# RS485.net
KiCad netlist of a schematic drawn in Altium Designer
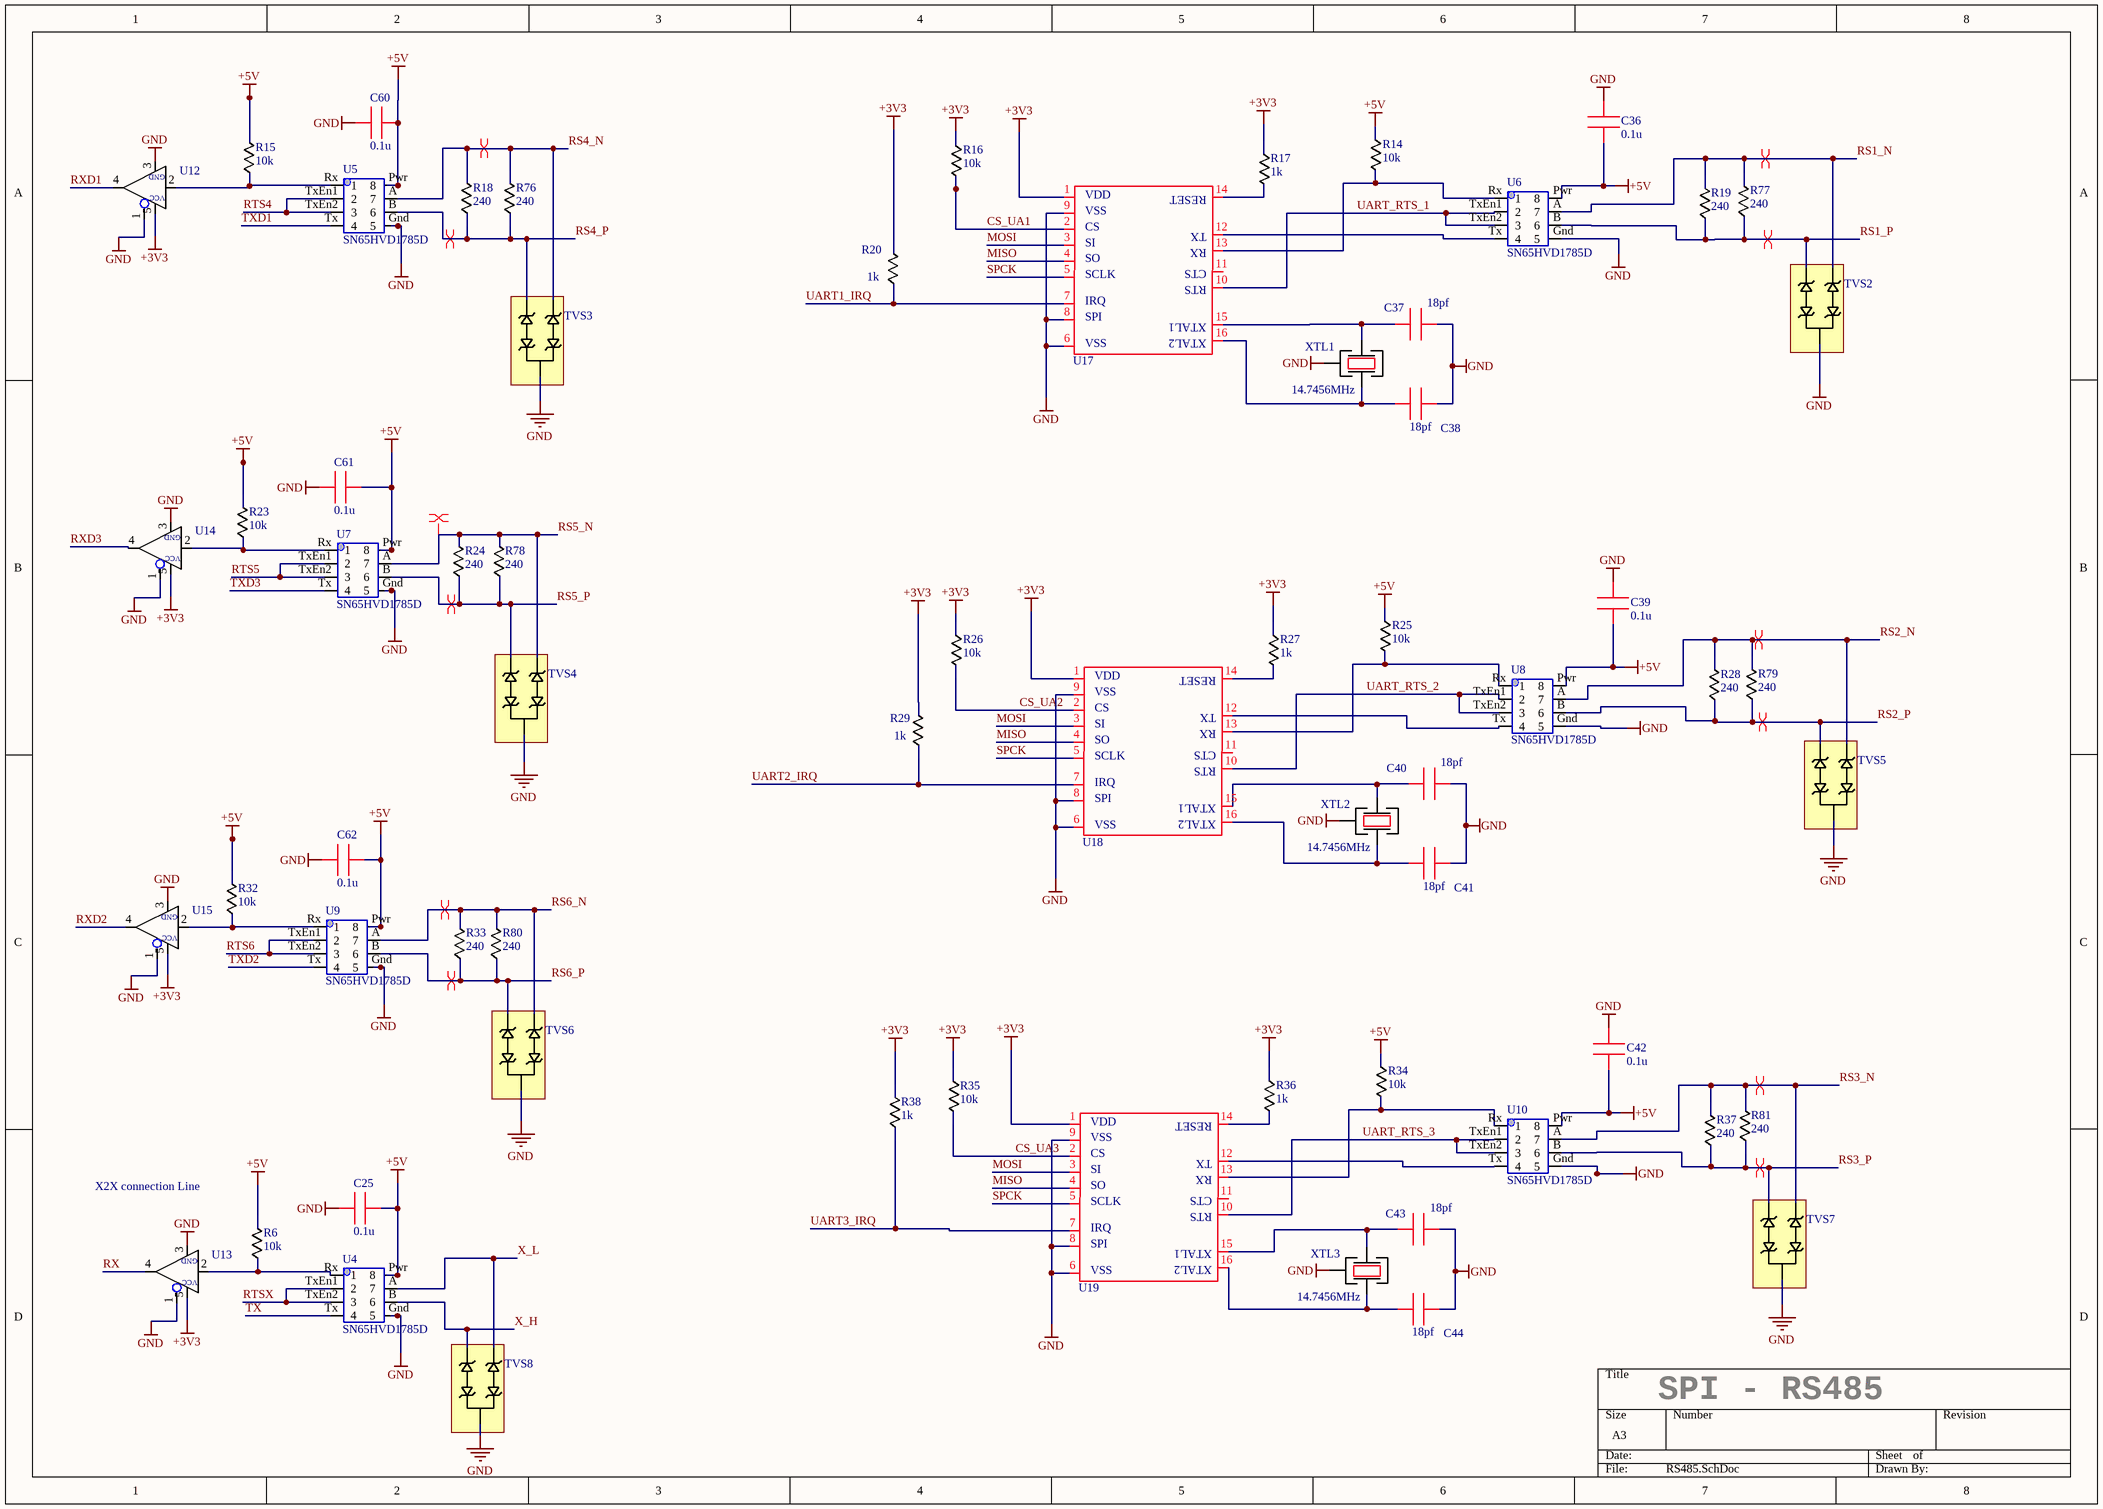
[diagram p0: RS485.SchDoc]

(export (version "E")
  (design (tool "Eeschema 10.0.6"))
  (components
    (comp (ref "C25") (value "0.1u") (footprint "0603 CAP") (libsource (lib "kontr") (part "Capasitor 0805")))
    (comp (ref "C36") (value "0.1u") (footprint "0603 CAP") (libsource (lib "kontr") (part "Capasitor 0805")))
    (comp (ref "C37")
      (value "18pf")
      (footprint "0603 CAP")
      (description "GRM1885C1H180JA01D")
      (libsource (lib "kontr") (part "Capasitor 0805"))
    )
    (comp (ref "C38")
      (value "18pf")
      (footprint "0603 CAP")
      (description "GRM1885C1H180JA01D")
      (libsource (lib "kontr") (part "Capasitor 0805"))
    )
    (comp (ref "C39") (value "0.1u") (footprint "0603 CAP") (libsource (lib "kontr") (part "Capasitor 0805")))
    (comp (ref "C40")
      (value "18pf")
      (footprint "0603 CAP")
      (description "GRM1885C1H180JA01D")
      (libsource (lib "kontr") (part "Capasitor 0805"))
    )
    (comp (ref "C41")
      (value "18pf")
      (footprint "0603 CAP")
      (description "GRM1885C1H180JA01D")
      (libsource (lib "kontr") (part "Capasitor 0805"))
    )
    (comp (ref "C42") (value "0.1u") (footprint "0603 CAP") (libsource (lib "kontr") (part "Capasitor 0805")))
    (comp (ref "C43")
      (value "18pf")
      (footprint "0603 CAP")
      (description "GRM1885C1H180JA01D")
      (libsource (lib "kontr") (part "Capasitor 0805"))
    )
    (comp (ref "C44")
      (value "18pf")
      (footprint "0603 CAP")
      (description "GRM1885C1H180JA01D")
      (libsource (lib "kontr") (part "Capasitor 0805"))
    )
    (comp (ref "C60") (value "0.1u") (footprint "0603 CAP") (libsource (lib "kontr") (part "Capasitor 0805")))
    (comp (ref "C61") (value "0.1u") (footprint "0603 CAP") (libsource (lib "kontr") (part "Capasitor 0805")))
    (comp (ref "C62") (value "0.1u") (footprint "0603 CAP") (libsource (lib "kontr") (part "Capasitor 0805")))
    (comp (ref "R6")
      (value "10k")
      (footprint "0603 - RES")
      (description "RC0603FR-078K2")
      (libsource (lib "kontr") (part "Resistor 0805"))
    )
    (comp (ref "R14")
      (value "10k")
      (footprint "0603 - RES")
      (description "RC0603FR-078K2")
      (libsource (lib "kontr") (part "Resistor 0805"))
    )
    (comp (ref "R15")
      (value "10k")
      (footprint "0603 - RES")
      (description "RC0603FR-078K2")
      (libsource (lib "kontr") (part "Resistor 0805"))
    )
    (comp (ref "R16")
      (value "10k")
      (footprint "0603 - RES")
      (description "RC0603JR-0710K")
      (libsource (lib "kontr") (part "Resistor 0805"))
    )
    (comp (ref "R17")
      (value "1k")
      (footprint "0603 - RES")
      (description "RC0603JR-0710K")
      (libsource (lib "kontr") (part "Resistor 0805"))
    )
    (comp (ref "R18")
      (value "240")
      (footprint "0603 - RES")
      (description "RC0603JR-07120R")
      (libsource (lib "kontr") (part "Resistor 0805"))
    )
    (comp (ref "R19")
      (value "240")
      (footprint "0603 - RES")
      (description "RC0603JR-07120R")
      (libsource (lib "kontr") (part "Resistor 0805"))
    )
    (comp (ref "R20")
      (value "1k")
      (footprint "0603 - RES")
      (description "RC0603JR-0710K")
      (libsource (lib "kontr") (part "Resistor 0805"))
    )
    (comp (ref "R23")
      (value "10k")
      (footprint "0603 - RES")
      (description "RC0603FR-078K2")
      (libsource (lib "kontr") (part "Resistor 0805"))
    )
    (comp (ref "R24")
      (value "240")
      (footprint "0603 - RES")
      (description "RC0603JR-07120R")
      (libsource (lib "kontr") (part "Resistor 0805"))
    )
    (comp (ref "R25")
      (value "10k")
      (footprint "0603 - RES")
      (description "RC0603FR-078K2")
      (libsource (lib "kontr") (part "Resistor 0805"))
    )
    (comp (ref "R26")
      (value "10k")
      (footprint "0603 - RES")
      (description "RC0603JR-0710K")
      (libsource (lib "kontr") (part "Resistor 0805"))
    )
    (comp (ref "R27")
      (value "1k")
      (footprint "0603 - RES")
      (description "RC0603JR-0710K")
      (libsource (lib "kontr") (part "Resistor 0805"))
    )
    (comp (ref "R28")
      (value "240")
      (footprint "0603 - RES")
      (description "RC0603JR-07120R")
      (libsource (lib "kontr") (part "Resistor 0805"))
    )
    (comp (ref "R29")
      (value "1k")
      (footprint "0603 - RES")
      (description "RC0603JR-0710K")
      (libsource (lib "kontr") (part "Resistor 0805"))
    )
    (comp (ref "R32")
      (value "10k")
      (footprint "0603 - RES")
      (description "RC0603FR-078K2")
      (libsource (lib "kontr") (part "Resistor 0805"))
    )
    (comp (ref "R33")
      (value "240")
      (footprint "0603 - RES")
      (description "RC0603JR-07120R")
      (libsource (lib "kontr") (part "Resistor 0805"))
    )
    (comp (ref "R34")
      (value "10k")
      (footprint "0603 - RES")
      (description "RC0603FR-078K2")
      (libsource (lib "kontr") (part "Resistor 0805"))
    )
    (comp (ref "R35")
      (value "10k")
      (footprint "0603 - RES")
      (description "RC0603JR-0710K")
      (libsource (lib "kontr") (part "Resistor 0805"))
    )
    (comp (ref "R36")
      (value "1k")
      (footprint "0603 - RES")
      (description "RC0603JR-0710K")
      (libsource (lib "kontr") (part "Resistor 0805"))
    )
    (comp (ref "R37")
      (value "240")
      (footprint "0603 - RES")
      (description "RC0603JR-07120R")
      (libsource (lib "kontr") (part "Resistor 0805"))
    )
    (comp (ref "R38")
      (value "1k")
      (footprint "0603 - RES")
      (description "RC0603JR-0710K")
      (libsource (lib "kontr") (part "Resistor 0805"))
    )
    (comp (ref "R76")
      (value "240")
      (footprint "0603 - RES")
      (description "RC0603JR-07120R")
      (libsource (lib "kontr") (part "Resistor 0805"))
    )
    (comp (ref "R77")
      (value "240")
      (footprint "0603 - RES")
      (description "RC0603JR-07120R")
      (libsource (lib "kontr") (part "Resistor 0805"))
    )
    (comp (ref "R78")
      (value "240")
      (footprint "0603 - RES")
      (description "RC0603JR-07120R")
      (libsource (lib "kontr") (part "Resistor 0805"))
    )
    (comp (ref "R79")
      (value "240")
      (footprint "0603 - RES")
      (description "RC0603JR-07120R")
      (libsource (lib "kontr") (part "Resistor 0805"))
    )
    (comp (ref "R80")
      (value "240")
      (footprint "0603 - RES")
      (description "RC0603JR-07120R")
      (libsource (lib "kontr") (part "Resistor 0805"))
    )
    (comp (ref "R81")
      (value "240")
      (footprint "0603 - RES")
      (description "RC0603JR-07120R")
      (libsource (lib "kontr") (part "Resistor 0805"))
    )
    (comp (ref "TVS2")
      (value "CDSOT23-SM712")
      (footprint "Sot23-3")
      (libsource (lib "kontr") (part "CDSOT23-SM712"))
    )
    (comp (ref "TVS3")
      (value "CDSOT23-SM712")
      (footprint "Sot23-3")
      (libsource (lib "kontr") (part "CDSOT23-SM712"))
    )
    (comp (ref "TVS4")
      (value "CDSOT23-SM712")
      (footprint "Sot23-3")
      (libsource (lib "kontr") (part "CDSOT23-SM712"))
    )
    (comp (ref "TVS5")
      (value "CDSOT23-SM712")
      (footprint "Sot23-3")
      (libsource (lib "kontr") (part "CDSOT23-SM712"))
    )
    (comp (ref "TVS6")
      (value "CDSOT23-SM712")
      (footprint "Sot23-3")
      (libsource (lib "kontr") (part "CDSOT23-SM712"))
    )
    (comp (ref "TVS7")
      (value "CDSOT23-SM712")
      (footprint "Sot23-3")
      (libsource (lib "kontr") (part "CDSOT23-SM712"))
    )
    (comp (ref "TVS8")
      (value "CDSOT23-SM712")
      (footprint "Sot23-3")
      (libsource (lib "kontr") (part "CDSOT23-SM712"))
    )
    (comp (ref "U4")
      (value "SN65HVD1785D")
      (footprint "MAX485 - duplicate")
      (libsource (lib "Schlib1") (part "MAX485"))
    )
    (comp (ref "U5")
      (value "SN65HVD1785D")
      (footprint "MAX485 - duplicate")
      (libsource (lib "Schlib1") (part "MAX485"))
    )
    (comp (ref "U6")
      (value "SN65HVD1785D")
      (footprint "MAX485 - duplicate")
      (libsource (lib "Schlib1") (part "MAX485"))
    )
    (comp (ref "U7")
      (value "SN65HVD1785D")
      (footprint "MAX485 - duplicate")
      (libsource (lib "Schlib1") (part "MAX485"))
    )
    (comp (ref "U8")
      (value "SN65HVD1785D")
      (footprint "MAX485 - duplicate")
      (libsource (lib "Schlib1") (part "MAX485"))
    )
    (comp (ref "U9")
      (value "SN65HVD1785D")
      (footprint "MAX485 - duplicate")
      (libsource (lib "Schlib1") (part "MAX485"))
    )
    (comp (ref "U10")
      (value "SN65HVD1785D")
      (footprint "MAX485 - duplicate")
      (libsource (lib "Schlib1") (part "MAX485"))
    )
    (comp (ref "U12")
      (value "74LVC1G125DCK")
      (footprint "74LVC1G125DCK")
      (libsource (lib "kontr") (part "74LVC1G125DCK"))
    )
    (comp (ref "U13")
      (value "74LVC1G125DCK")
      (footprint "74LVC1G125DCK")
      (libsource (lib "kontr") (part "74LVC1G125DCK"))
    )
    (comp (ref "U14")
      (value "74LVC1G125DCK")
      (footprint "74LVC1G125DCK")
      (libsource (lib "kontr") (part "74LVC1G125DCK"))
    )
    (comp (ref "U15")
      (value "74LVC1G125DCK")
      (footprint "74LVC1G125DCK")
      (libsource (lib "kontr") (part "74LVC1G125DCK"))
    )
    (comp (ref "U17")
      (value "SC16IS740")
      (footprint "SC16IS740")
      (libsource (lib "kontr") (part "SC16IS740"))
    )
    (comp (ref "U18")
      (value "SC16IS740")
      (footprint "SC16IS740")
      (libsource (lib "kontr") (part "SC16IS740"))
    )
    (comp (ref "U19")
      (value "SC16IS740")
      (footprint "SC16IS740")
      (libsource (lib "kontr") (part "SC16IS740"))
    )
    (comp (ref "XTL1")
      (value "14.7456MHz")
      (footprint "XTAL KX-7T")
      (description "Geyer KX-7 14.7456MHz")
      (libsource (lib "") (part "KX-7_1"))
    )
    (comp (ref "XTL2")
      (value "14.7456MHz")
      (footprint "XTAL KX-7T")
      (description "Geyer KX-7 14.7456MHz")
      (libsource (lib "PLC M3") (part "KX-7"))
    )
    (comp (ref "XTL3")
      (value "14.7456MHz")
      (footprint "XTAL KX-7T")
      (description "Geyer KX-7 14.7456MHz")
      (libsource (lib "") (part "KX-7_1"))
    )
  )
  (nets
    (net (code "1") (name "+3V3") (class "Default")
      (node (ref "R16") (pin "1") (pintype "passive"))
      (node (ref "R17") (pin "1") (pintype "passive"))
      (node (ref "R20") (pin "2") (pintype "passive"))
      (node (ref "R26") (pin "1") (pintype "passive"))
      (node (ref "R27") (pin "1") (pintype "passive"))
      (node (ref "R29") (pin "2") (pintype "passive"))
      (node (ref "R35") (pin "1") (pintype "passive"))
      (node (ref "R36") (pin "1") (pintype "passive"))
      (node (ref "R38") (pin "2") (pintype "passive"))
      (node (ref "U12") (pin "5") (pinfunction "7_5") (pintype "passive"))
      (node (ref "U13") (pin "5") (pinfunction "7_5") (pintype "passive"))
      (node (ref "U14") (pin "5") (pinfunction "7_5") (pintype "passive"))
      (node (ref "U15") (pin "5") (pinfunction "7_5") (pintype "passive"))
      (node (ref "U17") (pin "1") (pinfunction "4_1") (pintype "passive"))
      (node (ref "U18") (pin "1") (pinfunction "4_1") (pintype "passive"))
      (node (ref "U19") (pin "1") (pinfunction "4_1") (pintype "passive"))
    )
    (net (code "2") (name "+5V") (class "Default")
      (node (ref "C25") (pin "2") (pinfunction "2_2") (pintype "passive"))
      (node (ref "C36") (pin "2") (pinfunction "2_2") (pintype "passive"))
      (node (ref "C39") (pin "2") (pinfunction "2_2") (pintype "passive"))
      (node (ref "C42") (pin "2") (pinfunction "2_2") (pintype "passive"))
      (node (ref "C60") (pin "2") (pinfunction "2_2") (pintype "passive"))
      (node (ref "C61") (pin "2") (pinfunction "2_2") (pintype "passive"))
      (node (ref "C62") (pin "2") (pinfunction "2_2") (pintype "passive"))
      (node (ref "R14") (pin "1") (pintype "passive"))
      (node (ref "R15") (pin "2") (pintype "passive"))
      (node (ref "R23") (pin "2") (pintype "passive"))
      (node (ref "R25") (pin "1") (pintype "passive"))
      (node (ref "R32") (pin "2") (pintype "passive"))
      (node (ref "R34") (pin "1") (pintype "passive"))
      (node (ref "R6") (pin "2") (pintype "passive"))
      (node (ref "U10") (pin "Pwr") (pinfunction "8_Pwr") (pintype "passive"))
      (node (ref "U4") (pin "Pwr") (pinfunction "8_Pwr") (pintype "passive"))
      (node (ref "U5") (pin "Pwr") (pinfunction "8_Pwr") (pintype "passive"))
      (node (ref "U6") (pin "Pwr") (pinfunction "8_Pwr") (pintype "passive"))
      (node (ref "U7") (pin "Pwr") (pinfunction "8_Pwr") (pintype "passive"))
      (node (ref "U8") (pin "Pwr") (pinfunction "8_Pwr") (pintype "passive"))
      (node (ref "U9") (pin "Pwr") (pinfunction "8_Pwr") (pintype "passive"))
    )
    (net (code "3") (name "/CS_UA1") (class "Default")
      (node (ref "R16") (pin "2") (pintype "passive"))
      (node (ref "U17") (pin "2") (pinfunction "8_2") (pintype "passive"))
    )
    (net (code "4") (name "/CS_UA2") (class "Default")
      (node (ref "R26") (pin "2") (pintype "passive"))
      (node (ref "U18") (pin "2") (pinfunction "8_2") (pintype "passive"))
    )
    (net (code "5") (name "/CS_UA3") (class "Default")
      (node (ref "R35") (pin "2") (pintype "passive"))
      (node (ref "U19") (pin "2") (pinfunction "8_2") (pintype "passive"))
    )
    (net (code "6") (name "/MISO") (class "Default")
      (node (ref "U17") (pin "4") (pinfunction "8_4") (pintype "passive"))
      (node (ref "U18") (pin "4") (pinfunction "8_4") (pintype "passive"))
      (node (ref "U19") (pin "4") (pinfunction "8_4") (pintype "passive"))
    )
    (net (code "7") (name "/MOSI") (class "Default")
      (node (ref "U17") (pin "3") (pinfunction "8_3") (pintype "passive"))
      (node (ref "U18") (pin "3") (pinfunction "8_3") (pintype "passive"))
      (node (ref "U19") (pin "3") (pinfunction "8_3") (pintype "passive"))
    )
    (net (code "8") (name "/RS1_N") (class "Default")
      (node (ref "R19") (pin "2") (pintype "passive"))
      (node (ref "R77") (pin "2") (pintype "passive"))
      (node (ref "TVS2") (pin "1") (pinfunction "1_1") (pintype "passive"))
      (node (ref "U6") (pin "A") (pinfunction "7_A") (pintype "passive"))
    )
    (net (code "9") (name "/RS1_P") (class "Default")
      (node (ref "R19") (pin "1") (pintype "passive"))
      (node (ref "R77") (pin "1") (pintype "passive"))
      (node (ref "TVS2") (pin "2") (pinfunction "2_2") (pintype "passive"))
      (node (ref "U6") (pin "B") (pinfunction "6_B") (pintype "passive"))
    )
    (net (code "10") (name "/RS2_N") (class "Default")
      (node (ref "R28") (pin "2") (pintype "passive"))
      (node (ref "R79") (pin "2") (pintype "passive"))
      (node (ref "TVS5") (pin "1") (pinfunction "1_1") (pintype "passive"))
      (node (ref "U8") (pin "A") (pinfunction "7_A") (pintype "passive"))
    )
    (net (code "11") (name "/RS2_P") (class "Default")
      (node (ref "R28") (pin "1") (pintype "passive"))
      (node (ref "R79") (pin "1") (pintype "passive"))
      (node (ref "TVS5") (pin "2") (pinfunction "2_2") (pintype "passive"))
      (node (ref "U8") (pin "B") (pinfunction "6_B") (pintype "passive"))
    )
    (net (code "12") (name "/RS3_N") (class "Default")
      (node (ref "R37") (pin "2") (pintype "passive"))
      (node (ref "R81") (pin "2") (pintype "passive"))
      (node (ref "TVS7") (pin "1") (pinfunction "1_1") (pintype "passive"))
      (node (ref "U10") (pin "A") (pinfunction "7_A") (pintype "passive"))
    )
    (net (code "13") (name "/RS3_P") (class "Default")
      (node (ref "R37") (pin "1") (pintype "passive"))
      (node (ref "R81") (pin "1") (pintype "passive"))
      (node (ref "TVS7") (pin "2") (pinfunction "2_2") (pintype "passive"))
      (node (ref "U10") (pin "B") (pinfunction "6_B") (pintype "passive"))
    )
    (net (code "14") (name "/RS4_N") (class "Default")
      (node (ref "R18") (pin "2") (pintype "passive"))
      (node (ref "R76") (pin "2") (pintype "passive"))
      (node (ref "TVS3") (pin "1") (pinfunction "1_1") (pintype "passive"))
      (node (ref "U5") (pin "A") (pinfunction "7_A") (pintype "passive"))
    )
    (net (code "15") (name "/RS4_P") (class "Default")
      (node (ref "R18") (pin "1") (pintype "passive"))
      (node (ref "R76") (pin "1") (pintype "passive"))
      (node (ref "TVS3") (pin "2") (pinfunction "2_2") (pintype "passive"))
      (node (ref "U5") (pin "B") (pinfunction "6_B") (pintype "passive"))
    )
    (net (code "16") (name "/RS5_N") (class "Default")
      (node (ref "R24") (pin "2") (pintype "passive"))
      (node (ref "R78") (pin "2") (pintype "passive"))
      (node (ref "TVS4") (pin "1") (pinfunction "1_1") (pintype "passive"))
      (node (ref "U7") (pin "A") (pinfunction "7_A") (pintype "passive"))
    )
    (net (code "17") (name "/RS5_P") (class "Default")
      (node (ref "R24") (pin "1") (pintype "passive"))
      (node (ref "R78") (pin "1") (pintype "passive"))
      (node (ref "TVS4") (pin "2") (pinfunction "2_2") (pintype "passive"))
      (node (ref "U7") (pin "B") (pinfunction "6_B") (pintype "passive"))
    )
    (net (code "18") (name "/RS6_N") (class "Default")
      (node (ref "R33") (pin "2") (pintype "passive"))
      (node (ref "R80") (pin "2") (pintype "passive"))
      (node (ref "TVS6") (pin "1") (pinfunction "1_1") (pintype "passive"))
      (node (ref "U9") (pin "A") (pinfunction "7_A") (pintype "passive"))
    )
    (net (code "19") (name "/RS6_P") (class "Default")
      (node (ref "R33") (pin "1") (pintype "passive"))
      (node (ref "R80") (pin "1") (pintype "passive"))
      (node (ref "TVS6") (pin "2") (pinfunction "2_2") (pintype "passive"))
      (node (ref "U9") (pin "B") (pinfunction "6_B") (pintype "passive"))
    )
    (net (code "20") (name "/RTS4") (class "Default")
      (node (ref "U5") (pin "TxEn1") (pinfunction "2_TxEn1") (pintype "passive"))
      (node (ref "U5") (pin "TxEn2") (pinfunction "3_TxEn2") (pintype "passive"))
    )
    (net (code "21") (name "/RTS5") (class "Default")
      (node (ref "U7") (pin "TxEn1") (pinfunction "2_TxEn1") (pintype "passive"))
      (node (ref "U7") (pin "TxEn2") (pinfunction "3_TxEn2") (pintype "passive"))
    )
    (net (code "22") (name "/RTS6") (class "Default")
      (node (ref "U9") (pin "TxEn1") (pinfunction "2_TxEn1") (pintype "passive"))
      (node (ref "U9") (pin "TxEn2") (pinfunction "3_TxEn2") (pintype "passive"))
    )
    (net (code "23") (name "/RTSX") (class "Default")
      (node (ref "U4") (pin "TxEn1") (pinfunction "2_TxEn1") (pintype "passive"))
      (node (ref "U4") (pin "TxEn2") (pinfunction "3_TxEn2") (pintype "passive"))
    )
    (net (code "24") (name "/RX") (class "Default")
      (node (ref "U13") (pin "4") (pinfunction "7_4") (pintype "passive"))
    )
    (net (code "25") (name "/RXD1") (class "Default")
      (node (ref "U12") (pin "4") (pinfunction "7_4") (pintype "passive"))
    )
    (net (code "26") (name "/RXD2") (class "Default")
      (node (ref "U15") (pin "4") (pinfunction "7_4") (pintype "passive"))
    )
    (net (code "27") (name "/RXD3") (class "Default")
      (node (ref "U14") (pin "4") (pinfunction "7_4") (pintype "passive"))
    )
    (net (code "28") (name "/SPCK") (class "Default")
      (node (ref "U17") (pin "5") (pinfunction "8_5") (pintype "passive"))
      (node (ref "U18") (pin "5") (pinfunction "8_5") (pintype "passive"))
      (node (ref "U19") (pin "5") (pinfunction "8_5") (pintype "passive"))
    )
    (net (code "29") (name "/TX") (class "Default")
      (node (ref "U4") (pin "Tx") (pinfunction "4_Tx") (pintype "passive"))
    )
    (net (code "30") (name "/TXD1") (class "Default")
      (node (ref "U5") (pin "Tx") (pinfunction "4_Tx") (pintype "passive"))
    )
    (net (code "31") (name "/TXD2") (class "Default")
      (node (ref "U9") (pin "Tx") (pinfunction "4_Tx") (pintype "passive"))
    )
    (net (code "32") (name "/TXD3") (class "Default")
      (node (ref "U7") (pin "Tx") (pinfunction "4_Tx") (pintype "passive"))
    )
    (net (code "33") (name "/UART1_IRQ") (class "Default")
      (node (ref "R20") (pin "1") (pintype "passive"))
      (node (ref "U17") (pin "7") (pinfunction "8_7") (pintype "passive"))
    )
    (net (code "34") (name "/UART2_IRQ") (class "Default")
      (node (ref "R29") (pin "1") (pintype "passive"))
      (node (ref "U18") (pin "7") (pinfunction "8_7") (pintype "passive"))
    )
    (net (code "35") (name "/UART3_IRQ") (class "Default")
      (node (ref "R38") (pin "1") (pintype "passive"))
      (node (ref "U19") (pin "7") (pinfunction "8_7") (pintype "passive"))
    )
    (net (code "36") (name "/UART_RTS_1") (class "Default")
      (node (ref "U17") (pin "10") (pinfunction "8_10") (pintype "passive"))
      (node (ref "U6") (pin "TxEn1") (pinfunction "2_TxEn1") (pintype "passive"))
      (node (ref "U6") (pin "TxEn2") (pinfunction "3_TxEn2") (pintype "passive"))
    )
    (net (code "37") (name "/UART_RTS_2") (class "Default")
      (node (ref "U18") (pin "10") (pinfunction "8_10") (pintype "passive"))
      (node (ref "U8") (pin "TxEn1") (pinfunction "2_TxEn1") (pintype "passive"))
      (node (ref "U8") (pin "TxEn2") (pinfunction "3_TxEn2") (pintype "passive"))
    )
    (net (code "38") (name "/UART_RTS_3") (class "Default")
      (node (ref "U10") (pin "TxEn1") (pinfunction "2_TxEn1") (pintype "passive"))
      (node (ref "U10") (pin "TxEn2") (pinfunction "3_TxEn2") (pintype "passive"))
      (node (ref "U19") (pin "10") (pinfunction "8_10") (pintype "passive"))
    )
    (net (code "39") (name "/X_H") (class "Default")
      (node (ref "TVS8") (pin "2") (pinfunction "2_2") (pintype "passive"))
      (node (ref "U4") (pin "B") (pinfunction "6_B") (pintype "passive"))
    )
    (net (code "40") (name "/X_L") (class "Default")
      (node (ref "TVS8") (pin "1") (pinfunction "1_1") (pintype "passive"))
      (node (ref "U4") (pin "A") (pinfunction "7_A") (pintype "passive"))
    )
    (net (code "41") (name "GND") (class "Default")
      (node (ref "C25") (pin "1") (pinfunction "1_1") (pintype "passive"))
      (node (ref "C36") (pin "1") (pinfunction "1_1") (pintype "passive"))
      (node (ref "C37") (pin "1") (pinfunction "1_1") (pintype "passive"))
      (node (ref "C38") (pin "1") (pinfunction "1_1") (pintype "passive"))
      (node (ref "C39") (pin "1") (pinfunction "1_1") (pintype "passive"))
      (node (ref "C40") (pin "1") (pinfunction "1_1") (pintype "passive"))
      (node (ref "C41") (pin "1") (pinfunction "1_1") (pintype "passive"))
      (node (ref "C42") (pin "1") (pinfunction "1_1") (pintype "passive"))
      (node (ref "C43") (pin "1") (pinfunction "1_1") (pintype "passive"))
      (node (ref "C44") (pin "1") (pinfunction "1_1") (pintype "passive"))
      (node (ref "C60") (pin "1") (pinfunction "1_1") (pintype "passive"))
      (node (ref "C61") (pin "1") (pinfunction "1_1") (pintype "passive"))
      (node (ref "C62") (pin "1") (pinfunction "1_1") (pintype "passive"))
      (node (ref "TVS2") (pin "3") (pinfunction "3_3") (pintype "passive"))
      (node (ref "TVS3") (pin "3") (pinfunction "3_3") (pintype "passive"))
      (node (ref "TVS4") (pin "3") (pinfunction "3_3") (pintype "passive"))
      (node (ref "TVS5") (pin "3") (pinfunction "3_3") (pintype "passive"))
      (node (ref "TVS6") (pin "3") (pinfunction "3_3") (pintype "passive"))
      (node (ref "TVS7") (pin "3") (pinfunction "3_3") (pintype "passive"))
      (node (ref "TVS8") (pin "3") (pinfunction "3_3") (pintype "passive"))
      (node (ref "U10") (pin "Gnd") (pinfunction "5_Gnd") (pintype "passive"))
      (node (ref "U12") (pin "1") (pinfunction "7_1") (pintype "passive"))
      (node (ref "U12") (pin "3") (pinfunction "7_3") (pintype "passive"))
      (node (ref "U13") (pin "1") (pinfunction "7_1") (pintype "passive"))
      (node (ref "U13") (pin "3") (pinfunction "7_3") (pintype "passive"))
      (node (ref "U14") (pin "1") (pinfunction "7_1") (pintype "passive"))
      (node (ref "U14") (pin "3") (pinfunction "7_3") (pintype "passive"))
      (node (ref "U15") (pin "1") (pinfunction "7_1") (pintype "passive"))
      (node (ref "U15") (pin "3") (pinfunction "7_3") (pintype "passive"))
      (node (ref "U17") (pin "6") (pinfunction "8_6") (pintype "passive"))
      (node (ref "U17") (pin "8") (pinfunction "8_8") (pintype "passive"))
      (node (ref "U17") (pin "9") (pinfunction "9_9") (pintype "passive"))
      (node (ref "U18") (pin "6") (pinfunction "8_6") (pintype "passive"))
      (node (ref "U18") (pin "8") (pinfunction "8_8") (pintype "passive"))
      (node (ref "U18") (pin "9") (pinfunction "9_9") (pintype "passive"))
      (node (ref "U19") (pin "6") (pinfunction "8_6") (pintype "passive"))
      (node (ref "U19") (pin "8") (pinfunction "8_8") (pintype "passive"))
      (node (ref "U19") (pin "9") (pinfunction "9_9") (pintype "passive"))
      (node (ref "U4") (pin "Gnd") (pinfunction "5_Gnd") (pintype "passive"))
      (node (ref "U5") (pin "Gnd") (pinfunction "5_Gnd") (pintype "passive"))
      (node (ref "U6") (pin "Gnd") (pinfunction "5_Gnd") (pintype "passive"))
      (node (ref "U7") (pin "Gnd") (pinfunction "5_Gnd") (pintype "passive"))
      (node (ref "U8") (pin "Gnd") (pinfunction "5_Gnd") (pintype "passive"))
      (node (ref "U9") (pin "Gnd") (pinfunction "5_Gnd") (pintype "passive"))
      (node (ref "XTL1") (pin "2") (pinfunction "2_2") (pintype "passive"))
      (node (ref "XTL2") (pin "2") (pinfunction "2_2") (pintype "passive"))
      (node (ref "XTL3") (pin "2") (pinfunction "2_2") (pintype "passive"))
    )
    (net (code "42") (name "Net-(C37-Pad2)") (class "Default")
      (node (ref "C37") (pin "2") (pinfunction "2_2") (pintype "passive"))
      (node (ref "U17") (pin "15") (pinfunction "8_15") (pintype "passive"))
      (node (ref "XTL1") (pin "1") (pinfunction "5_1") (pintype "passive"))
    )
    (net (code "43") (name "Net-(C38-Pad2)") (class "Default")
      (node (ref "C38") (pin "2") (pinfunction "2_2") (pintype "passive"))
      (node (ref "U17") (pin "16") (pinfunction "8_16") (pintype "passive"))
      (node (ref "XTL1") (pin "3") (pinfunction "5_3") (pintype "passive"))
    )
    (net (code "44") (name "Net-(C40-Pad2)") (class "Default")
      (node (ref "C40") (pin "2") (pinfunction "2_2") (pintype "passive"))
      (node (ref "U18") (pin "15") (pinfunction "8_15") (pintype "passive"))
      (node (ref "XTL2") (pin "1") (pinfunction "5_1") (pintype "passive"))
    )
    (net (code "45") (name "Net-(C41-Pad2)") (class "Default")
      (node (ref "C41") (pin "2") (pinfunction "2_2") (pintype "passive"))
      (node (ref "U18") (pin "16") (pinfunction "8_16") (pintype "passive"))
      (node (ref "XTL2") (pin "3") (pinfunction "5_3") (pintype "passive"))
    )
    (net (code "46") (name "Net-(C43-Pad2)") (class "Default")
      (node (ref "C43") (pin "2") (pinfunction "2_2") (pintype "passive"))
      (node (ref "U19") (pin "15") (pinfunction "8_15") (pintype "passive"))
      (node (ref "XTL3") (pin "1") (pinfunction "5_1") (pintype "passive"))
    )
    (net (code "47") (name "Net-(C44-Pad2)") (class "Default")
      (node (ref "C44") (pin "2") (pinfunction "2_2") (pintype "passive"))
      (node (ref "U19") (pin "16") (pinfunction "8_16") (pintype "passive"))
      (node (ref "XTL3") (pin "3") (pinfunction "5_3") (pintype "passive"))
    )
    (net (code "48") (name "Net-(R17-Pad2)") (class "Default")
      (node (ref "R17") (pin "2") (pintype "passive"))
      (node (ref "U17") (pin "14") (pinfunction "8_14") (pintype "passive"))
    )
    (net (code "49") (name "Net-(R27-Pad2)") (class "Default")
      (node (ref "R27") (pin "2") (pintype "passive"))
      (node (ref "U18") (pin "14") (pinfunction "8_14") (pintype "passive"))
    )
    (net (code "50") (name "Net-(R36-Pad2)") (class "Default")
      (node (ref "R36") (pin "2") (pintype "passive"))
      (node (ref "U19") (pin "14") (pinfunction "8_14") (pintype "passive"))
    )
    (net (code "51") (name "Net-(U4-1)") (class "Default")
      (node (ref "R6") (pin "1") (pintype "passive"))
      (node (ref "U13") (pin "2") (pinfunction "7_2") (pintype "passive"))
      (node (ref "U4") (pin "Rx") (pinfunction "1_Rx") (pintype "passive"))
    )
    (net (code "52") (name "Net-(U5-1)") (class "Default")
      (node (ref "R15") (pin "1") (pintype "passive"))
      (node (ref "U12") (pin "2") (pinfunction "7_2") (pintype "passive"))
      (node (ref "U5") (pin "Rx") (pinfunction "1_Rx") (pintype "passive"))
    )
    (net (code "53") (name "Net-(U6-1)") (class "Default")
      (node (ref "R14") (pin "2") (pintype "passive"))
      (node (ref "U17") (pin "13") (pinfunction "8_13") (pintype "passive"))
      (node (ref "U6") (pin "Rx") (pinfunction "1_Rx") (pintype "passive"))
    )
    (net (code "54") (name "Net-(U6-4)") (class "Default")
      (node (ref "U17") (pin "12") (pinfunction "8_12") (pintype "passive"))
      (node (ref "U6") (pin "Tx") (pinfunction "4_Tx") (pintype "passive"))
    )
    (net (code "55") (name "Net-(U7-1)") (class "Default")
      (node (ref "R23") (pin "1") (pintype "passive"))
      (node (ref "U14") (pin "2") (pinfunction "7_2") (pintype "passive"))
      (node (ref "U7") (pin "Rx") (pinfunction "1_Rx") (pintype "passive"))
    )
    (net (code "56") (name "Net-(U8-1)") (class "Default")
      (node (ref "R25") (pin "2") (pintype "passive"))
      (node (ref "U18") (pin "13") (pinfunction "8_13") (pintype "passive"))
      (node (ref "U8") (pin "Rx") (pinfunction "1_Rx") (pintype "passive"))
    )
    (net (code "57") (name "Net-(U8-4)") (class "Default")
      (node (ref "U18") (pin "12") (pinfunction "8_12") (pintype "passive"))
      (node (ref "U8") (pin "Tx") (pinfunction "4_Tx") (pintype "passive"))
    )
    (net (code "58") (name "Net-(U9-1)") (class "Default")
      (node (ref "R32") (pin "1") (pintype "passive"))
      (node (ref "U15") (pin "2") (pinfunction "7_2") (pintype "passive"))
      (node (ref "U9") (pin "Rx") (pinfunction "1_Rx") (pintype "passive"))
    )
    (net (code "59") (name "Net-(U10-1)") (class "Default")
      (node (ref "R34") (pin "2") (pintype "passive"))
      (node (ref "U10") (pin "Rx") (pinfunction "1_Rx") (pintype "passive"))
      (node (ref "U19") (pin "13") (pinfunction "8_13") (pintype "passive"))
    )
    (net (code "60") (name "Net-(U10-4)") (class "Default")
      (node (ref "U10") (pin "Tx") (pinfunction "4_Tx") (pintype "passive"))
      (node (ref "U19") (pin "12") (pinfunction "8_12") (pintype "passive"))
    )
    (net (code "61") (name "unconnected-(U17-8-Pad11)") (class "Default")
      (node (ref "U17") (pin "11") (pinfunction "8_11") (pintype "passive"))
    )
    (net (code "62") (name "unconnected-(U18-8-Pad11)") (class "Default")
      (node (ref "U18") (pin "11") (pinfunction "8_11") (pintype "passive"))
    )
    (net (code "63") (name "unconnected-(U19-8-Pad11)") (class "Default")
      (node (ref "U19") (pin "11") (pinfunction "8_11") (pintype "passive"))
    )
  )
)
